# Microcontroller.net
KiCad netlist of a schematic drawn in Altium Designer
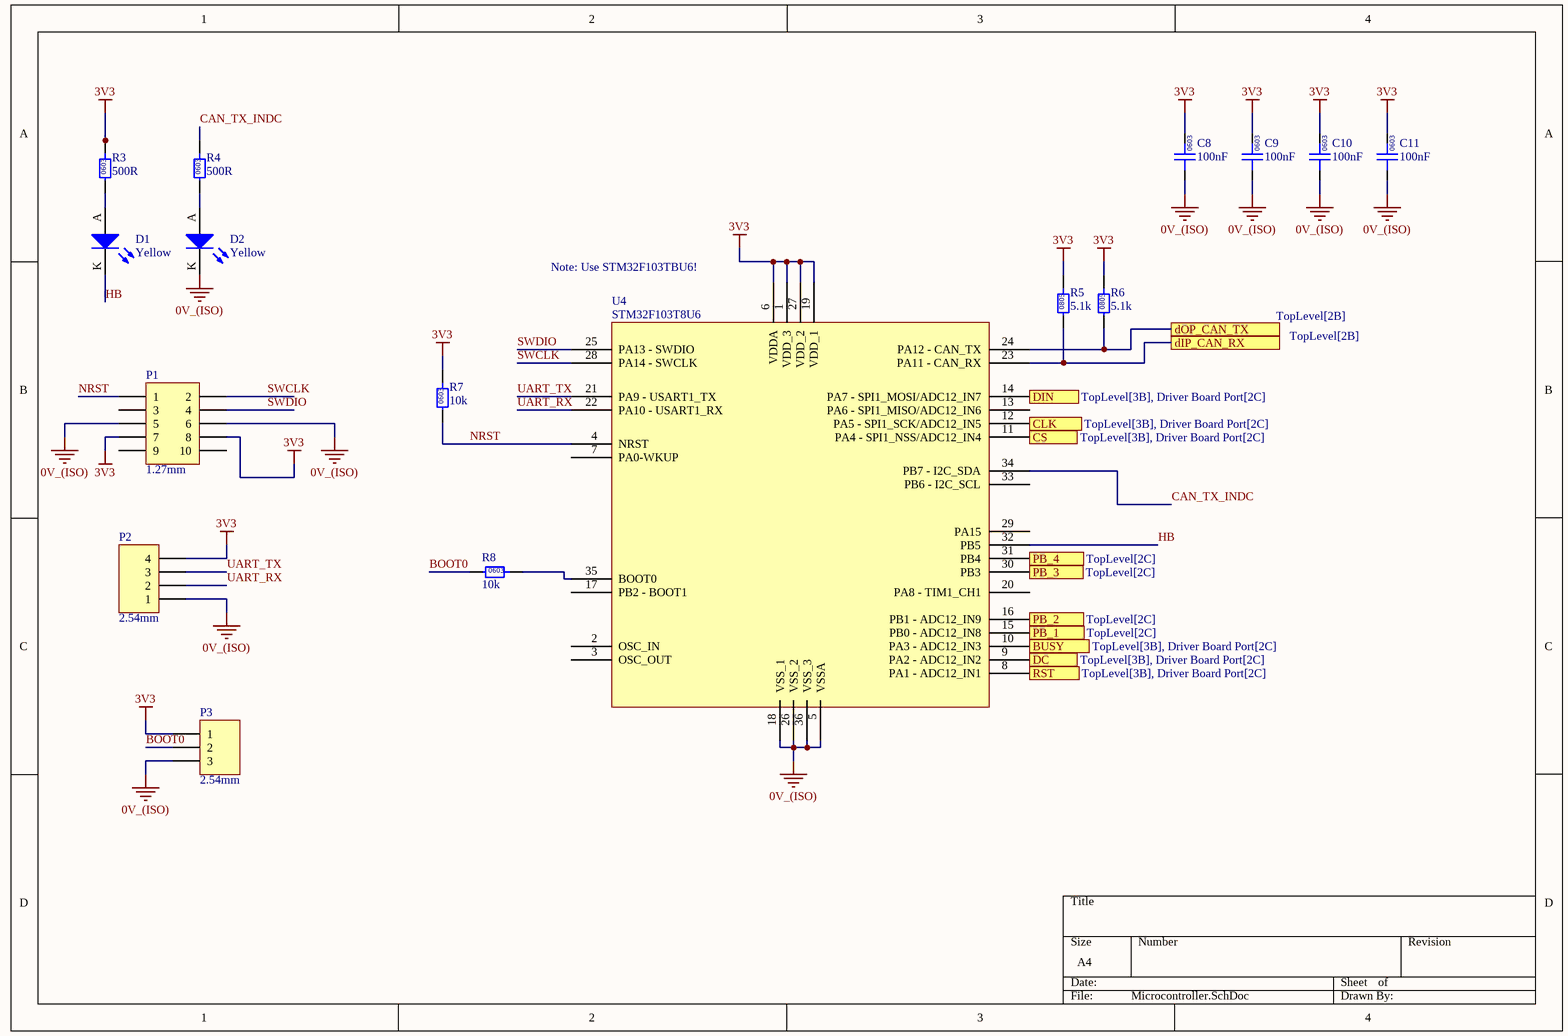
[diagram p0: Microcontroller.SchDoc]

(export (version "E")
  (design (tool "Eeschema 10.0.6"))
  (components
    (comp (ref "C8")
      (value "100nF")
      (footprint "0603")
      (fields
        (field (name "PART NUMBER") "GCM188L81H104KA57D")
        (field (name "MANUFACTURER") "muRata")
        (field (name "TOLERANCE") "±10%")
      )
      (libsource (lib "ts_standard_library") (part "Capacitor 0603"))
    )
    (comp (ref "C9")
      (value "100nF")
      (footprint "0603")
      (fields
        (field (name "PART NUMBER") "GCM188L81H104KA57D")
        (field (name "MANUFACTURER") "muRata")
        (field (name "TOLERANCE") "±10%")
      )
      (libsource (lib "ts_standard_library") (part "Capacitor 0603"))
    )
    (comp (ref "C10")
      (value "100nF")
      (footprint "0603")
      (fields
        (field (name "PART NUMBER") "GCM188L81H104KA57D")
        (field (name "MANUFACTURER") "muRata")
        (field (name "TOLERANCE") "±10%")
      )
      (libsource (lib "ts_standard_library") (part "Capacitor 0603"))
    )
    (comp (ref "C11")
      (value "100nF")
      (footprint "0603")
      (fields
        (field (name "PART NUMBER") "GCM188L81H104KA57D")
        (field (name "MANUFACTURER") "muRata")
        (field (name "TOLERANCE") "±10%")
      )
      (libsource (lib "ts_standard_library") (part "Capacitor 0603"))
    )
    (comp (ref "D1")
      (value "Yellow")
      (footprint "0805 LED")
      (description "Yellow LED Indication - Discrete 1.75V 0805 (2012 Metric)")
      (fields (field (name "PART NUMBER") "SML-211YTT86") (field (name "MANUFACTURER") "ROHM Semiconductor"))
      (libsource (lib "ts_standard_library") (part "LED"))
    )
    (comp (ref "D2")
      (value "Yellow")
      (footprint "0805 LED")
      (description "Yellow LED Indication - Discrete 1.75V 0805 (2012 Metric)")
      (fields (field (name "PART NUMBER") "SML-211YTT86") (field (name "MANUFACTURER") "ROHM Semiconductor"))
      (libsource (lib "ts_standard_library") (part "LED"))
    )
    (comp (ref "P1")
      (value "1.27mm")
      (footprint "3221-10-0300-00")
      (fields
        (field (name "PART NUMBER") "SMD 1.27mm Header 2x5 (3221-10-0300-00)")
        (field (name "CONTACT") "NA")
      )
      (libsource (lib "ts_standard_connectors") (part "Header 2x5"))
    )
    (comp (ref "P2")
      (value "2.54mm")
      (footprint "TH 2.54mm Header 1x4")
      (fields (field (name "PART NUMBER") "TH 2.54mm Header 1x4") (field (name "CONTACT") "NA"))
      (libsource (lib "ts_standard_connectors") (part "Header 1x4"))
    )
    (comp (ref "P3")
      (value "2.54mm")
      (footprint "TH 2.54mm Header 1x3")
      (fields (field (name "PART NUMBER") "TH 2.54mm Header 1x3") (field (name "CONTACT") "NA"))
      (libsource (lib "ts_standard_connectors") (part "Header 1x3"))
    )
    (comp (ref "R3")
      (value "500R")
      (footprint "0603")
      (fields
        (field (name "PART NUMBER") "RT0603BRD07500RL")
        (field (name "MANUFACTURER") "YAGEO")
        (field (name "TOLERANCE") "0.01")
      )
      (libsource (lib "ts_standard_library") (part "Resistor 0603"))
    )
    (comp (ref "R4")
      (value "500R")
      (footprint "0603")
      (fields
        (field (name "PART NUMBER") "RT0603BRD07500RL")
        (field (name "MANUFACTURER") "YAGEO")
        (field (name "TOLERANCE") "0.01")
      )
      (libsource (lib "ts_standard_library") (part "Resistor 0603"))
    )
    (comp (ref "R5")
      (value "5.1k")
      (footprint "0805")
      (fields
        (field (name "PART NUMBER") "RC0805FR075K1L")
        (field (name "MANUFACTURER") "YAGEO")
        (field (name "TOLERANCE") "0.01")
      )
      (libsource (lib "ts_standard_library") (part "Resistor 0805"))
    )
    (comp (ref "R6")
      (value "5.1k")
      (footprint "0805")
      (fields
        (field (name "PART NUMBER") "RC0805FR075K1L")
        (field (name "MANUFACTURER") "YAGEO")
        (field (name "TOLERANCE") "0.01")
      )
      (libsource (lib "ts_standard_library") (part "Resistor 0805"))
    )
    (comp (ref "R7")
      (value "10k")
      (footprint "0603")
      (fields
        (field (name "PART NUMBER") "RC0603FR-0710KL")
        (field (name "MANUFACTURER") "YAGEO")
        (field (name "TOLERANCE") "0.01")
      )
      (libsource (lib "ts_standard_library") (part "Resistor 0603"))
    )
    (comp (ref "R8")
      (value "10k")
      (footprint "0603")
      (fields
        (field (name "PART NUMBER") "RC0603FR-0710KL")
        (field (name "MANUFACTURER") "YAGEO")
        (field (name "TOLERANCE") "0.01")
      )
      (libsource (lib "ts_standard_library") (part "Resistor 0603"))
    )
    (comp (ref "U4")
      (value "STM32F103T8U6")
      (footprint "STM_QFN-36")
      (description "ARM® Cortex®-M3 STM32F1 Microcontroller IC 32-Bit 72MHz 64KB (64K x 8) FLASH QFN")
      (fields (field (name "MANUFACTURER") "ST Microelectronics"))
      (libsource (lib "ts_standard_library") (part "STM32F103T8U6"))
    )
  )
  (nets
    (net (code "1") (name "/BOOT0") (class "Default")
      (node (ref "P3") (pin "2") (pinfunction "2_2") (pintype "passive"))
      (node (ref "R8") (pin "1") (pinfunction "1_1") (pintype "passive"))
    )
    (net (code "2") (name "/BUSY") (class "Default")
      (node (ref "U4") (pin "10") (pinfunction "PA3_-_ADC12_IN3_10") (pintype "passive"))
    )
    (net (code "3") (name "/CAN_TX_INDC") (class "Default")
      (node (ref "R4") (pin "2") (pinfunction "2_2") (pintype "passive"))
      (node (ref "U4") (pin "34") (pinfunction "PB7_-_I2C_SDA_34") (pintype "passive"))
    )
    (net (code "4") (name "/CLK") (class "Default")
      (node (ref "U4") (pin "12") (pinfunction "PA5_-_SPI1_SCK/ADC12_IN5_12") (pintype "passive"))
    )
    (net (code "5") (name "/CS") (class "Default")
      (node (ref "U4") (pin "11") (pinfunction "PA4_-_SPI1_NSS/ADC12_IN4_11") (pintype "passive"))
    )
    (net (code "6") (name "/DC") (class "Default")
      (node (ref "U4") (pin "9") (pinfunction "PA2_-_ADC12_IN2_9") (pintype "passive"))
    )
    (net (code "7") (name "/DIN") (class "Default")
      (node (ref "U4") (pin "14") (pinfunction "PA7_-_SPI1_MOSI/ADC12_IN7_14") (pintype "passive"))
    )
    (net (code "8") (name "/HB") (class "Default")
      (node (ref "D1") (pin "K") (pinfunction "K_K") (pintype "passive"))
      (node (ref "U4") (pin "32") (pinfunction "PB5_32") (pintype "passive"))
    )
    (net (code "9") (name "/NRST") (class "Default")
      (node (ref "P1") (pin "1") (pinfunction "1_1") (pintype "passive"))
      (node (ref "R7") (pin "1") (pinfunction "1_1") (pintype "passive"))
      (node (ref "U4") (pin "4") (pinfunction "NRST_4") (pintype "passive"))
    )
    (net (code "10") (name "/PB_1") (class "Default")
      (node (ref "U4") (pin "15") (pinfunction "PB0_-_ADC12_IN8_15") (pintype "passive"))
    )
    (net (code "11") (name "/PB_2") (class "Default")
      (node (ref "U4") (pin "16") (pinfunction "PB1_-_ADC12_IN9_16") (pintype "passive"))
    )
    (net (code "12") (name "/PB_3") (class "Default")
      (node (ref "U4") (pin "30") (pinfunction "PB3_30") (pintype "passive"))
    )
    (net (code "13") (name "/PB_4") (class "Default")
      (node (ref "U4") (pin "31") (pinfunction "PB4_31") (pintype "passive"))
    )
    (net (code "14") (name "/RST") (class "Default")
      (node (ref "U4") (pin "8") (pinfunction "PA1_-_ADC12_IN1_8") (pintype "passive"))
    )
    (net (code "15") (name "/SWCLK") (class "Default")
      (node (ref "P1") (pin "2") (pinfunction "2_2") (pintype "passive"))
      (node (ref "U4") (pin "28") (pinfunction "PA14_-_SWCLK_28") (pintype "passive"))
    )
    (net (code "16") (name "/SWDIO") (class "Default")
      (node (ref "P1") (pin "4") (pinfunction "4_4") (pintype "passive"))
      (node (ref "U4") (pin "25") (pinfunction "PA13_-_SWDIO_25") (pintype "passive"))
    )
    (net (code "17") (name "/UART_RX") (class "Default")
      (node (ref "P2") (pin "2") (pinfunction "2_2") (pintype "passive"))
      (node (ref "U4") (pin "22") (pinfunction "PA10_-_USART1_RX_22") (pintype "passive"))
    )
    (net (code "18") (name "/UART_TX") (class "Default")
      (node (ref "P2") (pin "3") (pinfunction "3_3") (pintype "passive"))
      (node (ref "U4") (pin "21") (pinfunction "PA9_-_USART1_TX_21") (pintype "passive"))
    )
    (net (code "19") (name "/dIP_CAN_RX") (class "Default")
      (node (ref "R5") (pin "1") (pinfunction "1_1") (pintype "passive"))
      (node (ref "U4") (pin "23") (pinfunction "PA11_-_CAN_RX_23") (pintype "passive"))
    )
    (net (code "20") (name "/dOP_CAN_TX") (class "Default")
      (node (ref "R6") (pin "1") (pinfunction "1_1") (pintype "passive"))
      (node (ref "U4") (pin "24") (pinfunction "PA12_-_CAN_TX_24") (pintype "passive"))
    )
    (net (code "21") (name "0V_(ISO)") (class "Default")
      (node (ref "C10") (pin "1") (pinfunction "1_1") (pintype "passive"))
      (node (ref "C11") (pin "1") (pinfunction "1_1") (pintype "passive"))
      (node (ref "C8") (pin "1") (pinfunction "1_1") (pintype "passive"))
      (node (ref "C9") (pin "1") (pinfunction "1_1") (pintype "passive"))
      (node (ref "D2") (pin "K") (pinfunction "K_K") (pintype "passive"))
      (node (ref "P1") (pin "5") (pinfunction "5_5") (pintype "passive"))
      (node (ref "P1") (pin "6") (pinfunction "6_6") (pintype "passive"))
      (node (ref "P2") (pin "1") (pinfunction "1_1") (pintype "passive"))
      (node (ref "P3") (pin "3") (pinfunction "3_3") (pintype "passive"))
      (node (ref "U4") (pin "18") (pinfunction "VSS_1_18") (pintype "passive"))
      (node (ref "U4") (pin "26") (pinfunction "VSS_2_26") (pintype "passive"))
      (node (ref "U4") (pin "36") (pinfunction "VSS_3_36") (pintype "passive"))
      (node (ref "U4") (pin "5") (pinfunction "VSSA_5") (pintype "passive"))
    )
    (net (code "22") (name "3V3") (class "Default")
      (node (ref "C10") (pin "2") (pinfunction "2_2") (pintype "passive"))
      (node (ref "C11") (pin "2") (pinfunction "2_2") (pintype "passive"))
      (node (ref "C8") (pin "2") (pinfunction "2_2") (pintype "passive"))
      (node (ref "C9") (pin "2") (pinfunction "2_2") (pintype "passive"))
      (node (ref "P1") (pin "7") (pinfunction "7_7") (pintype "passive"))
      (node (ref "P1") (pin "8") (pinfunction "8_8") (pintype "passive"))
      (node (ref "P2") (pin "4") (pinfunction "4_4") (pintype "passive"))
      (node (ref "P3") (pin "1") (pinfunction "1_1") (pintype "passive"))
      (node (ref "R3") (pin "2") (pinfunction "2_2") (pintype "passive"))
      (node (ref "R5") (pin "2") (pinfunction "2_2") (pintype "passive"))
      (node (ref "R6") (pin "2") (pinfunction "2_2") (pintype "passive"))
      (node (ref "R7") (pin "2") (pinfunction "2_2") (pintype "passive"))
      (node (ref "U4") (pin "1") (pinfunction "VDD_3_1") (pintype "passive"))
      (node (ref "U4") (pin "19") (pinfunction "VDD_1_19") (pintype "passive"))
      (node (ref "U4") (pin "27") (pinfunction "VDD_2_27") (pintype "passive"))
      (node (ref "U4") (pin "6") (pinfunction "VDDA_6") (pintype "passive"))
    )
    (net (code "23") (name "Net-(D1-PadA)") (class "Default")
      (node (ref "D1") (pin "A") (pinfunction "A_A") (pintype "passive"))
      (node (ref "R3") (pin "1") (pinfunction "1_1") (pintype "passive"))
    )
    (net (code "24") (name "Net-(D2-PadA)") (class "Default")
      (node (ref "D2") (pin "A") (pinfunction "A_A") (pintype "passive"))
      (node (ref "R4") (pin "1") (pinfunction "1_1") (pintype "passive"))
    )
    (net (code "25") (name "Net-(U4-BOOT0)") (class "Default")
      (node (ref "R8") (pin "2") (pinfunction "2_2") (pintype "passive"))
      (node (ref "U4") (pin "35") (pinfunction "BOOT0_35") (pintype "passive"))
    )
    (net (code "26") (name "unconnected-(P1-Pad3)") (class "Default")
      (node (ref "P1") (pin "3") (pinfunction "3_3") (pintype "passive"))
    )
    (net (code "27") (name "unconnected-(P1-Pad9)") (class "Default")
      (node (ref "P1") (pin "9") (pinfunction "9_9") (pintype "passive"))
    )
    (net (code "28") (name "unconnected-(P1-Pad10)") (class "Default")
      (node (ref "P1") (pin "10") (pinfunction "10_10") (pintype "passive"))
    )
    (net (code "29") (name "unconnected-(U4-OSC_IN-Pad2)") (class "Default")
      (node (ref "U4") (pin "2") (pinfunction "OSC_IN_2") (pintype "passive"))
    )
    (net (code "30") (name "unconnected-(U4-OSC_OUT-Pad3)") (class "Default")
      (node (ref "U4") (pin "3") (pinfunction "OSC_OUT_3") (pintype "passive"))
    )
    (net (code "31") (name "unconnected-(U4-PA0-WKUP-Pad7)") (class "Default")
      (node (ref "U4") (pin "7") (pinfunction "PA0-WKUP_7") (pintype "passive"))
    )
    (net (code "32") (name "unconnected-(U4-PA6_-_SPI1_MISO{slash}ADC12_IN6-Pad13)") (class "Default")
      (node (ref "U4") (pin "13") (pinfunction "PA6_-_SPI1_MISO/ADC12_IN6_13") (pintype "passive"))
    )
    (net (code "33") (name "unconnected-(U4-PA8_-_TIM1_CH1-Pad20)") (class "Default")
      (node (ref "U4") (pin "20") (pinfunction "PA8_-_TIM1_CH1_20") (pintype "passive"))
    )
    (net (code "34") (name "unconnected-(U4-PA15-Pad29)") (class "Default")
      (node (ref "U4") (pin "29") (pinfunction "PA15_29") (pintype "passive"))
    )
    (net (code "35") (name "unconnected-(U4-PB2_-_BOOT1-Pad17)") (class "Default")
      (node (ref "U4") (pin "17") (pinfunction "PB2_-_BOOT1_17") (pintype "passive"))
    )
    (net (code "36") (name "unconnected-(U4-PB6_-_I2C_SCL-Pad33)") (class "Default")
      (node (ref "U4") (pin "33") (pinfunction "PB6_-_I2C_SCL_33") (pintype "passive"))
    )
  )
)
